# USB.net
KiCad netlist of a schematic drawn in Altium Designer
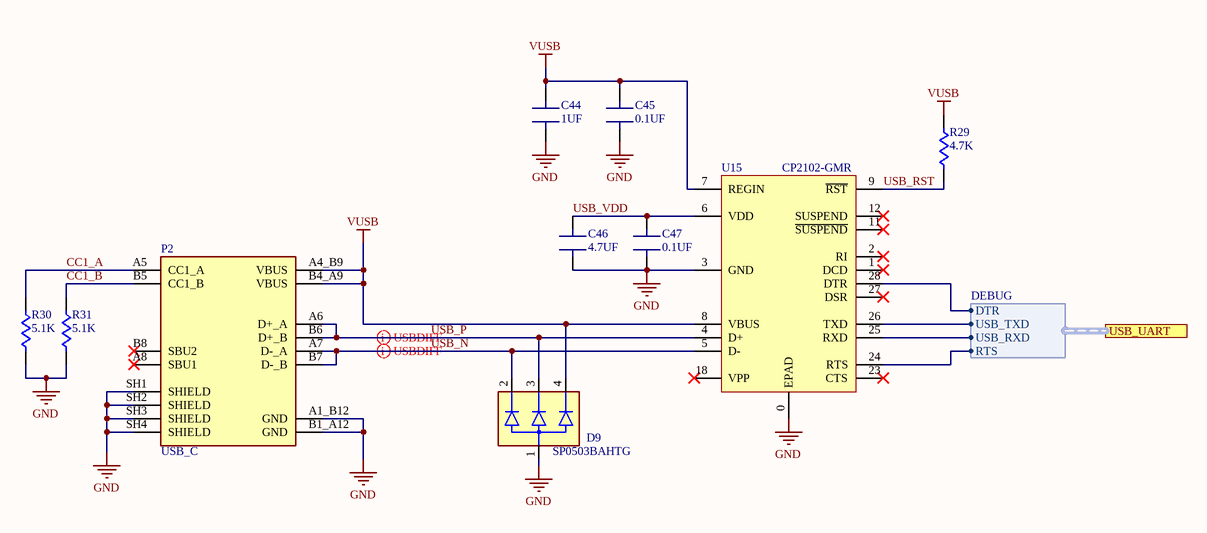
[diagram p0: USB.SchDoc]

(export (version "E")
  (design (tool "Eeschema 10.0.6"))
  (components
    (comp (ref "C44")
      (value "1UF")
      (footprint "CAP: 0603")
      (description "CAP SMD 0603")
      (libsource (lib "HZSchLib") (part "CAP 0603"))
    )
    (comp (ref "C45")
      (value "0.1UF")
      (footprint "CAP: 0603")
      (description "CAP SMD 0603")
      (libsource (lib "HZSchLib") (part "CAP 0603"))
    )
    (comp (ref "C46")
      (value "4.7UF")
      (footprint "CAP: 0805")
      (description "CAP SMD 0805")
      (libsource (lib "HZSchLib") (part "CAP 0805"))
    )
    (comp (ref "C47")
      (value "0.1UF")
      (footprint "CAP: 0603")
      (description "CAP SMD 0603")
      (libsource (lib "HZSchLib") (part "CAP 0603"))
    )
    (comp (ref "D9")
      (value "SP0503BAHTG")
      (footprint "SOT143-4")
      (description "SP050xBA Series 8.5 V 30 pF Triple Uni-Directional TVS Avalanche Diode-SOT143-4")
      (fields (field (name "MANUFACTURER") "Littelfuse"))
      (libsource (lib "HZSchLib") (part "SP0503BAHTG"))
    )
    (comp (ref "P2")
      (value "USB_C")
      (footprint "AMPHENOL_12402012E212A")
      (description "USB Connectors USB2.0, Type C, Top mount, CH 1.68mm, Dual Row SMT")
      (fields
        (field (name "MANUFACTURER") "Amphenol")
        (field (name "MANUFACTURER PART NUMBER") "12402012E212A")
      )
      (libsource (lib "HZSchLib") (part "12402012E212A"))
    )
    (comp (ref "R29")
      (value "4.7K")
      (footprint "RES: 0603")
      (description "RES SMD 0603")
      (libsource (lib "HZSchLib") (part "RES 0603"))
    )
    (comp (ref "R30")
      (value "5.1K")
      (footprint "RES: 0603")
      (description "RES SMD 0603")
      (libsource (lib "HZSchLib") (part "RES 0603"))
    )
    (comp (ref "R31")
      (value "5.1K")
      (footprint "RES: 0603")
      (description "RES SMD 0603")
      (libsource (lib "HZSchLib") (part "RES 0603"))
    )
    (comp (ref "U15")
      (value "CP2102-GMR")
      (footprint "28-QFN (5x5)")
      (description "Interface IC low speed/full speed USB to UART bridge USB 2.0 3.3V, CP2102-GMR, VFQFN-28")
      (fields (field (name "MANUFACTURER") "Silicon Labs"))
      (libsource (lib "HZSchLib") (part "CP2102-GMR"))
    )
  )
  (nets
    (net (code "2") (name "/CC1_A") (class "Default")
      (node (ref "P2") (pin "A5") (pinfunction "CC1_A_A5") (pintype "passive"))
      (node (ref "R30") (pin "2") (pinfunction "2_2") (pintype "passive"))
    )
    (net (code "3") (name "/CC1_B") (class "Default")
      (node (ref "P2") (pin "B5") (pinfunction "CC1_B_B5") (pintype "passive"))
      (node (ref "R31") (pin "2") (pinfunction "2_2") (pintype "passive"))
    )
    (net (code "4") (name "/DTR") (class "Default")
      (node (ref "U15") (pin "28") (pinfunction "DTR_28") (pintype "passive"))
    )
    (net (code "5") (name "/RTS") (class "Default")
      (node (ref "U15") (pin "24") (pinfunction "RTS_24") (pintype "passive"))
    )
    (net (code "6") (name "/USB_N") (class "Default")
      (node (ref "D9") (pin "2") (pinfunction "2_2") (pintype "passive"))
      (node (ref "P2") (pin "A7") (pinfunction "D-_A_A7") (pintype "passive"))
      (node (ref "P2") (pin "B7") (pinfunction "D-_B_B7") (pintype "passive"))
      (node (ref "U15") (pin "5") (pinfunction "D-_5") (pintype "passive"))
    )
    (net (code "7") (name "/USB_P") (class "Default")
      (node (ref "D9") (pin "3") (pinfunction "3_3") (pintype "passive"))
      (node (ref "P2") (pin "A6") (pinfunction "D+_A_A6") (pintype "passive"))
      (node (ref "P2") (pin "B6") (pinfunction "D+_B_B6") (pintype "passive"))
      (node (ref "U15") (pin "4") (pinfunction "D+_4") (pintype "passive"))
    )
    (net (code "8") (name "/USB_RST") (class "Default")
      (node (ref "R29") (pin "1") (pinfunction "1_1") (pintype "passive"))
      (node (ref "U15") (pin "9") (pinfunction "~{RST}_9") (pintype "passive"))
    )
    (net (code "9") (name "/USB_RXD") (class "Default")
      (node (ref "U15") (pin "25") (pinfunction "RXD_25") (pintype "passive"))
    )
    (net (code "10") (name "/USB_TXD") (class "Default")
      (node (ref "U15") (pin "26") (pinfunction "TXD_26") (pintype "passive"))
    )
    (net (code "11") (name "/USB_VDD") (class "Default")
      (node (ref "C46") (pin "2") (pinfunction "B_2") (pintype "passive"))
      (node (ref "C47") (pin "2") (pinfunction "B_2") (pintype "passive"))
      (node (ref "U15") (pin "6") (pinfunction "VDD_6") (pintype "passive"))
    )
    (net (code "13") (name "GND") (class "Default")
      (node (ref "C44") (pin "1") (pinfunction "A_1") (pintype "passive"))
      (node (ref "C45") (pin "1") (pinfunction "A_1") (pintype "passive"))
      (node (ref "C46") (pin "1") (pinfunction "A_1") (pintype "passive"))
      (node (ref "C47") (pin "1") (pinfunction "A_1") (pintype "passive"))
      (node (ref "D9") (pin "1") (pinfunction "1_1") (pintype "passive"))
      (node (ref "P2") (pin "A1_B12") (pinfunction "GND_A1_B12") (pintype "passive"))
      (node (ref "P2") (pin "B1_A12") (pinfunction "GND_B1_A12") (pintype "passive"))
      (node (ref "P2") (pin "SH1") (pinfunction "SHIELD_SH1") (pintype "passive"))
      (node (ref "P2") (pin "SH2") (pinfunction "SHIELD_SH2") (pintype "passive"))
      (node (ref "P2") (pin "SH3") (pinfunction "SHIELD_SH3") (pintype "passive"))
      (node (ref "P2") (pin "SH4") (pinfunction "SHIELD_SH4") (pintype "passive"))
      (node (ref "R30") (pin "1") (pinfunction "1_1") (pintype "passive"))
      (node (ref "R31") (pin "1") (pinfunction "1_1") (pintype "passive"))
      (node (ref "U15") (pin "0") (pinfunction "EPAD_0") (pintype "passive"))
      (node (ref "U15") (pin "3") (pinfunction "GND_3") (pintype "passive"))
    )
    (net (code "14") (name "VUSB") (class "Default")
      (node (ref "C44") (pin "2") (pinfunction "B_2") (pintype "passive"))
      (node (ref "C45") (pin "2") (pinfunction "B_2") (pintype "passive"))
      (node (ref "D9") (pin "4") (pinfunction "4_4") (pintype "passive"))
      (node (ref "P2") (pin "A4_B9") (pinfunction "VBUS_A4_B9") (pintype "passive"))
      (node (ref "P2") (pin "B4_A9") (pinfunction "VBUS_B4_A9") (pintype "passive"))
      (node (ref "R29") (pin "2") (pinfunction "2_2") (pintype "passive"))
      (node (ref "U15") (pin "7") (pinfunction "REGIN_7") (pintype "passive"))
      (node (ref "U15") (pin "8") (pinfunction "VBUS_8") (pintype "passive"))
    )
    (net (code "15") (name "unconnected-(P2-SBU1-PadA8)") (class "Default")
      (node (ref "P2") (pin "A8") (pinfunction "SBU1_A8") (pintype "passive+no_connect"))
    )
    (net (code "16") (name "unconnected-(P2-SBU2-PadB8)") (class "Default")
      (node (ref "P2") (pin "B8") (pinfunction "SBU2_B8") (pintype "passive+no_connect"))
    )
    (net (code "17") (name "unconnected-(U15-CTS-Pad23)") (class "Default")
      (node (ref "U15") (pin "23") (pinfunction "CTS_23") (pintype "passive+no_connect"))
    )
    (net (code "18") (name "unconnected-(U15-DCD-Pad1)") (class "Default")
      (node (ref "U15") (pin "1") (pinfunction "DCD_1") (pintype "passive+no_connect"))
    )
    (net (code "19") (name "unconnected-(U15-DSR-Pad27)") (class "Default")
      (node (ref "U15") (pin "27") (pinfunction "DSR_27") (pintype "passive+no_connect"))
    )
    (net (code "20") (name "unconnected-(U15-RI-Pad2)") (class "Default")
      (node (ref "U15") (pin "2") (pinfunction "RI_2") (pintype "passive+no_connect"))
    )
    (net (code "21") (name "unconnected-(U15-SUSPEND-Pad12)") (class "Default")
      (node (ref "U15") (pin "12") (pinfunction "SUSPEND_12") (pintype "passive+no_connect"))
    )
    (net (code "22") (name "unconnected-(U15-VPP-Pad18)") (class "Default")
      (node (ref "U15") (pin "18") (pinfunction "VPP_18") (pintype "passive+no_connect"))
    )
    (net (code "23") (name "unconnected-(U15-~{SUSPEND}-Pad11)") (class "Default")
      (node (ref "U15") (pin "11") (pinfunction "~{SUSPEND}_11") (pintype "passive+no_connect"))
    )
  )
)
